# PSU_ZXCL330_3V3.net
KiCad netlist of a schematic drawn in Altium Designer
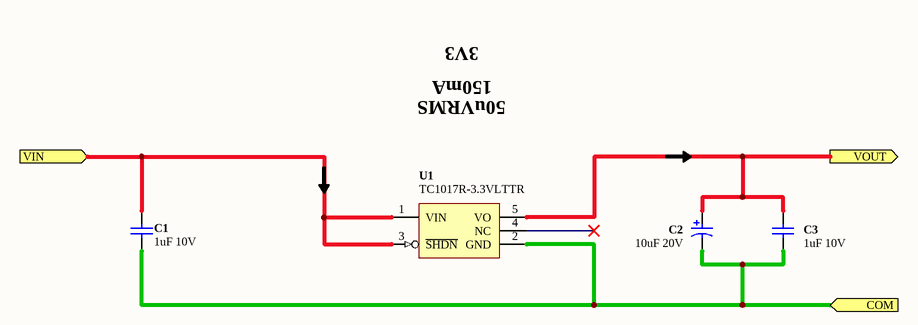
[diagram p0: PSU_ZXCL330_3V3.SchDoc]

(export (version "E")
  (design (tool "Eeschema 10.0.6"))
  (components
    (comp (ref "C1")
      (value "1uF 10V")
      (footprint "CAPC1005-STAR")
      (description "Capacitor, Ceramic, 1uF 10% 10V 0402 (1005) X5R")
      (fields (field (name "TOLERANCE") "10 %"))
      (libsource (lib "AltiumDesignLibrary") (part "CAP-NP"))
    )
    (comp (ref "C2")
      (value "10uF 20V")
      (footprint "CAPC3528-STAR")
      (description "Capacitor, Tantalum, 10uF 10% 20V MCCT-B (3528)")
      (fields (field (name "TOLERANCE") "10 %"))
      (libsource (lib "AltiumDesignLibrary") (part "CAP-P"))
    )
    (comp (ref "C3")
      (value "1uF 10V")
      (footprint "CAPC1005-STAR")
      (description "Capacitor, Ceramic, 1uF 10% 10V 0402 (1005) X5R")
      (fields (field (name "TOLERANCE") "10 %"))
      (libsource (lib "AltiumDesignLibrary") (part "CAP-NP"))
    )
    (comp (ref "U1")
      (value "TC1017R-3.3VLTTR")
      (footprint "SOT65P210X80-5N")
      (description "TC1017R-3.3VLTTR, 3.3V Micropower Low Dropout Regulator, 5-Pin SC70-5")
      (libsource (lib "AltiumDesignLibrary") (part "TC1017R"))
    )
  )
  (nets
    (net (code "1") (name "/COM") (class "Default")
      (node (ref "C1") (pin "1") (pinfunction "1_1") (pintype "passive"))
      (node (ref "C2") (pin "2") (pinfunction "2_2") (pintype "passive"))
      (node (ref "C3") (pin "1") (pinfunction "1_1") (pintype "passive"))
      (node (ref "U1") (pin "2") (pinfunction "GND_2") (pintype "power_in"))
    )
    (net (code "2") (name "/VIN") (class "Default")
      (node (ref "C1") (pin "2") (pinfunction "2_2") (pintype "passive"))
      (node (ref "U1") (pin "1") (pinfunction "VIN_1") (pintype "power_in"))
      (node (ref "U1") (pin "3") (pinfunction "~{SHDN}_3") (pintype "input"))
    )
    (net (code "3") (name "/VOUT") (class "Default")
      (node (ref "C2") (pin "1") (pinfunction "1_1") (pintype "passive"))
      (node (ref "C3") (pin "2") (pinfunction "2_2") (pintype "passive"))
      (node (ref "U1") (pin "5") (pinfunction "VO_5") (pintype "power_in"))
    )
    (net (code "4") (name "unconnected-(U1-NC-Pad4)") (class "Default")
      (node (ref "U1") (pin "4") (pinfunction "NC_4") (pintype "passive+no_connect"))
    )
  )
)
